# LEDBox.net
KiCad netlist of a schematic drawn in EAGLE
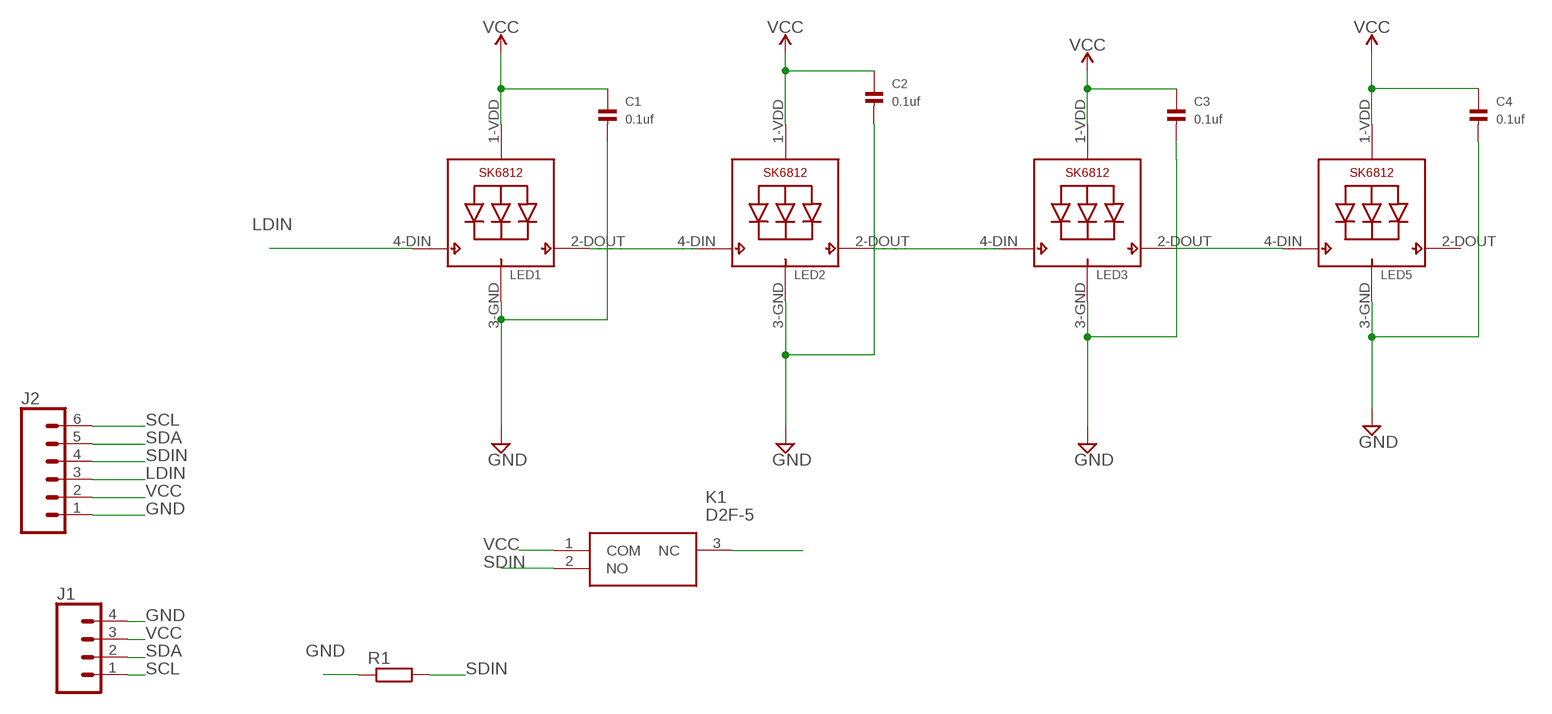
[diagram p0: schematic, sheet 1]

(export (version "E")
  (design (tool "Eeschema 10.0.6"))
  (components
    (comp (ref "C1")
      (value "0.1uf")
      (footprint "eagle-import:1206")
      (libsource (lib "eagle-import") (part "CAP_CERAMIC1206"))
    )
    (comp (ref "C2")
      (value "0.1uf")
      (footprint "eagle-import:1206")
      (libsource (lib "eagle-import") (part "CAP_CERAMIC1206"))
    )
    (comp (ref "C3")
      (value "0.1uf")
      (footprint "eagle-import:1206")
      (libsource (lib "eagle-import") (part "CAP_CERAMIC1206"))
    )
    (comp (ref "C4")
      (value "0.1uf")
      (footprint "eagle-import:1206")
      (libsource (lib "eagle-import") (part "CAP_CERAMIC1206"))
    )
    (comp (ref "J1")
      (value "CONN_041X04_NO_SILK")
      (footprint "eagle-import:1X04_NO_SILK")
      (libsource (lib "eagle-import") (part "CONN_041X04_NO_SILK"))
    )
    (comp (ref "J2")
      (value "CONN_06SMD-1MM")
      (footprint "eagle-import:1X06-1MM")
      (libsource (lib "eagle-import") (part "CONN_06SMD-1MM"))
    )
    (comp (ref "K1")
      (value "D2F-5")
      (footprint "eagle-import:SHDR3W100P0X508_1X3_1280X580X5")
      (fields (field (name "MOUSER_PART_NUMBER") "653-D2F-5"))
      (libsource (lib "eagle-import") (part "D2F-5"))
    )
    (comp (ref "LED1")
      (value "SK6812_5050")
      (footprint "eagle-import:LED5050")
      (libsource (lib "eagle-import") (part "SK6812_5050"))
    )
    (comp (ref "LED2")
      (value "SK6812_5050")
      (footprint "eagle-import:LED5050")
      (libsource (lib "eagle-import") (part "SK6812_5050"))
    )
    (comp (ref "LED3")
      (value "SK6812_5050")
      (footprint "eagle-import:LED5050")
      (libsource (lib "eagle-import") (part "SK6812_5050"))
    )
    (comp (ref "LED5")
      (value "SK6812_5050")
      (footprint "eagle-import:LED5050")
      (libsource (lib "eagle-import") (part "SK6812_5050"))
    )
    (comp (ref "R1")
      (value "RR3216")
      (footprint "eagle-import:R3216")
      (libsource (lib "eagle-import") (part "RR3216"))
    )
  )
  (nets
    (net (code "1") (name "/LDIN") (class "Default")
      (node (ref "J2") (pin "3") (pinfunction "3_3") (pintype "passive"))
      (node (ref "LED1") (pin "4-DIN") (pinfunction "DI_4-DIN") (pintype "input"))
    )
    (net (code "2") (name "/SCL") (class "Default")
      (node (ref "J1") (pin "1") (pinfunction "1_1") (pintype "passive"))
      (node (ref "J2") (pin "6") (pinfunction "6_6") (pintype "passive"))
    )
    (net (code "3") (name "/SDA") (class "Default")
      (node (ref "J1") (pin "2") (pinfunction "2_2") (pintype "passive"))
      (node (ref "J2") (pin "5") (pinfunction "5_5") (pintype "passive"))
    )
    (net (code "4") (name "/SDIN") (class "Default")
      (node (ref "J2") (pin "4") (pinfunction "4_4") (pintype "passive"))
      (node (ref "K1") (pin "2") (pinfunction "NO_2") (pintype "bidirectional"))
      (node (ref "R1") (pin "2") (pinfunction "2_2") (pintype "passive"))
    )
    (net (code "5") (name "GND") (class "Default")
      (node (ref "C1") (pin "2") (pinfunction "P$2_2") (pintype "passive"))
      (node (ref "C2") (pin "2") (pinfunction "P$2_2") (pintype "passive"))
      (node (ref "C3") (pin "2") (pinfunction "P$2_2") (pintype "passive"))
      (node (ref "C4") (pin "2") (pinfunction "P$2_2") (pintype "passive"))
      (node (ref "J1") (pin "4") (pinfunction "4_4") (pintype "passive"))
      (node (ref "J2") (pin "1") (pinfunction "1_1") (pintype "passive"))
      (node (ref "LED1") (pin "3-GND") (pinfunction "GND_3-GND") (pintype "power_in"))
      (node (ref "LED2") (pin "3-GND") (pinfunction "GND_3-GND") (pintype "power_in"))
      (node (ref "LED3") (pin "3-GND") (pinfunction "GND_3-GND") (pintype "power_in"))
      (node (ref "LED5") (pin "3-GND") (pinfunction "GND_3-GND") (pintype "power_in"))
      (node (ref "R1") (pin "1") (pinfunction "1_1") (pintype "passive"))
    )
    (net (code "6") (name "Net-(LED1-DO)") (class "Default")
      (node (ref "LED1") (pin "2-DOUT") (pinfunction "DO_2-DOUT") (pintype "output"))
      (node (ref "LED2") (pin "4-DIN") (pinfunction "DI_4-DIN") (pintype "input"))
    )
    (net (code "7") (name "Net-(LED2-DO)") (class "Default")
      (node (ref "LED2") (pin "2-DOUT") (pinfunction "DO_2-DOUT") (pintype "output"))
      (node (ref "LED3") (pin "4-DIN") (pinfunction "DI_4-DIN") (pintype "input"))
    )
    (net (code "8") (name "Net-(LED3-DO)") (class "Default")
      (node (ref "LED3") (pin "2-DOUT") (pinfunction "DO_2-DOUT") (pintype "output"))
      (node (ref "LED5") (pin "4-DIN") (pinfunction "DI_4-DIN") (pintype "input"))
    )
    (net (code "9") (name "VCC") (class "Default")
      (node (ref "C1") (pin "1") (pinfunction "P$1_1") (pintype "passive"))
      (node (ref "C2") (pin "1") (pinfunction "P$1_1") (pintype "passive"))
      (node (ref "C3") (pin "1") (pinfunction "P$1_1") (pintype "passive"))
      (node (ref "C4") (pin "1") (pinfunction "P$1_1") (pintype "passive"))
      (node (ref "J1") (pin "3") (pinfunction "3_3") (pintype "passive"))
      (node (ref "J2") (pin "2") (pinfunction "2_2") (pintype "passive"))
      (node (ref "K1") (pin "1") (pinfunction "COM_1") (pintype "bidirectional"))
      (node (ref "LED1") (pin "1-VDD") (pinfunction "VDD_1-VDD") (pintype "power_in"))
      (node (ref "LED2") (pin "1-VDD") (pinfunction "VDD_1-VDD") (pintype "power_in"))
      (node (ref "LED3") (pin "1-VDD") (pinfunction "VDD_1-VDD") (pintype "power_in"))
      (node (ref "LED5") (pin "1-VDD") (pinfunction "VDD_1-VDD") (pintype "power_in"))
    )
    (net (code "10") (name "unconnected-(K1-NC-Pad3)") (class "Default")
      (node (ref "K1") (pin "3") (pinfunction "NC_3") (pintype "no_connect"))
    )
    (net (code "11") (name "unconnected-(LED5-DO-Pad2-DOUT)") (class "Default")
      (node (ref "LED5") (pin "2-DOUT") (pinfunction "DO_2-DOUT") (pintype "output"))
    )
  )
)
